# Sprite_CC1310_Development.net
KiCad netlist of a schematic drawn in EAGLE
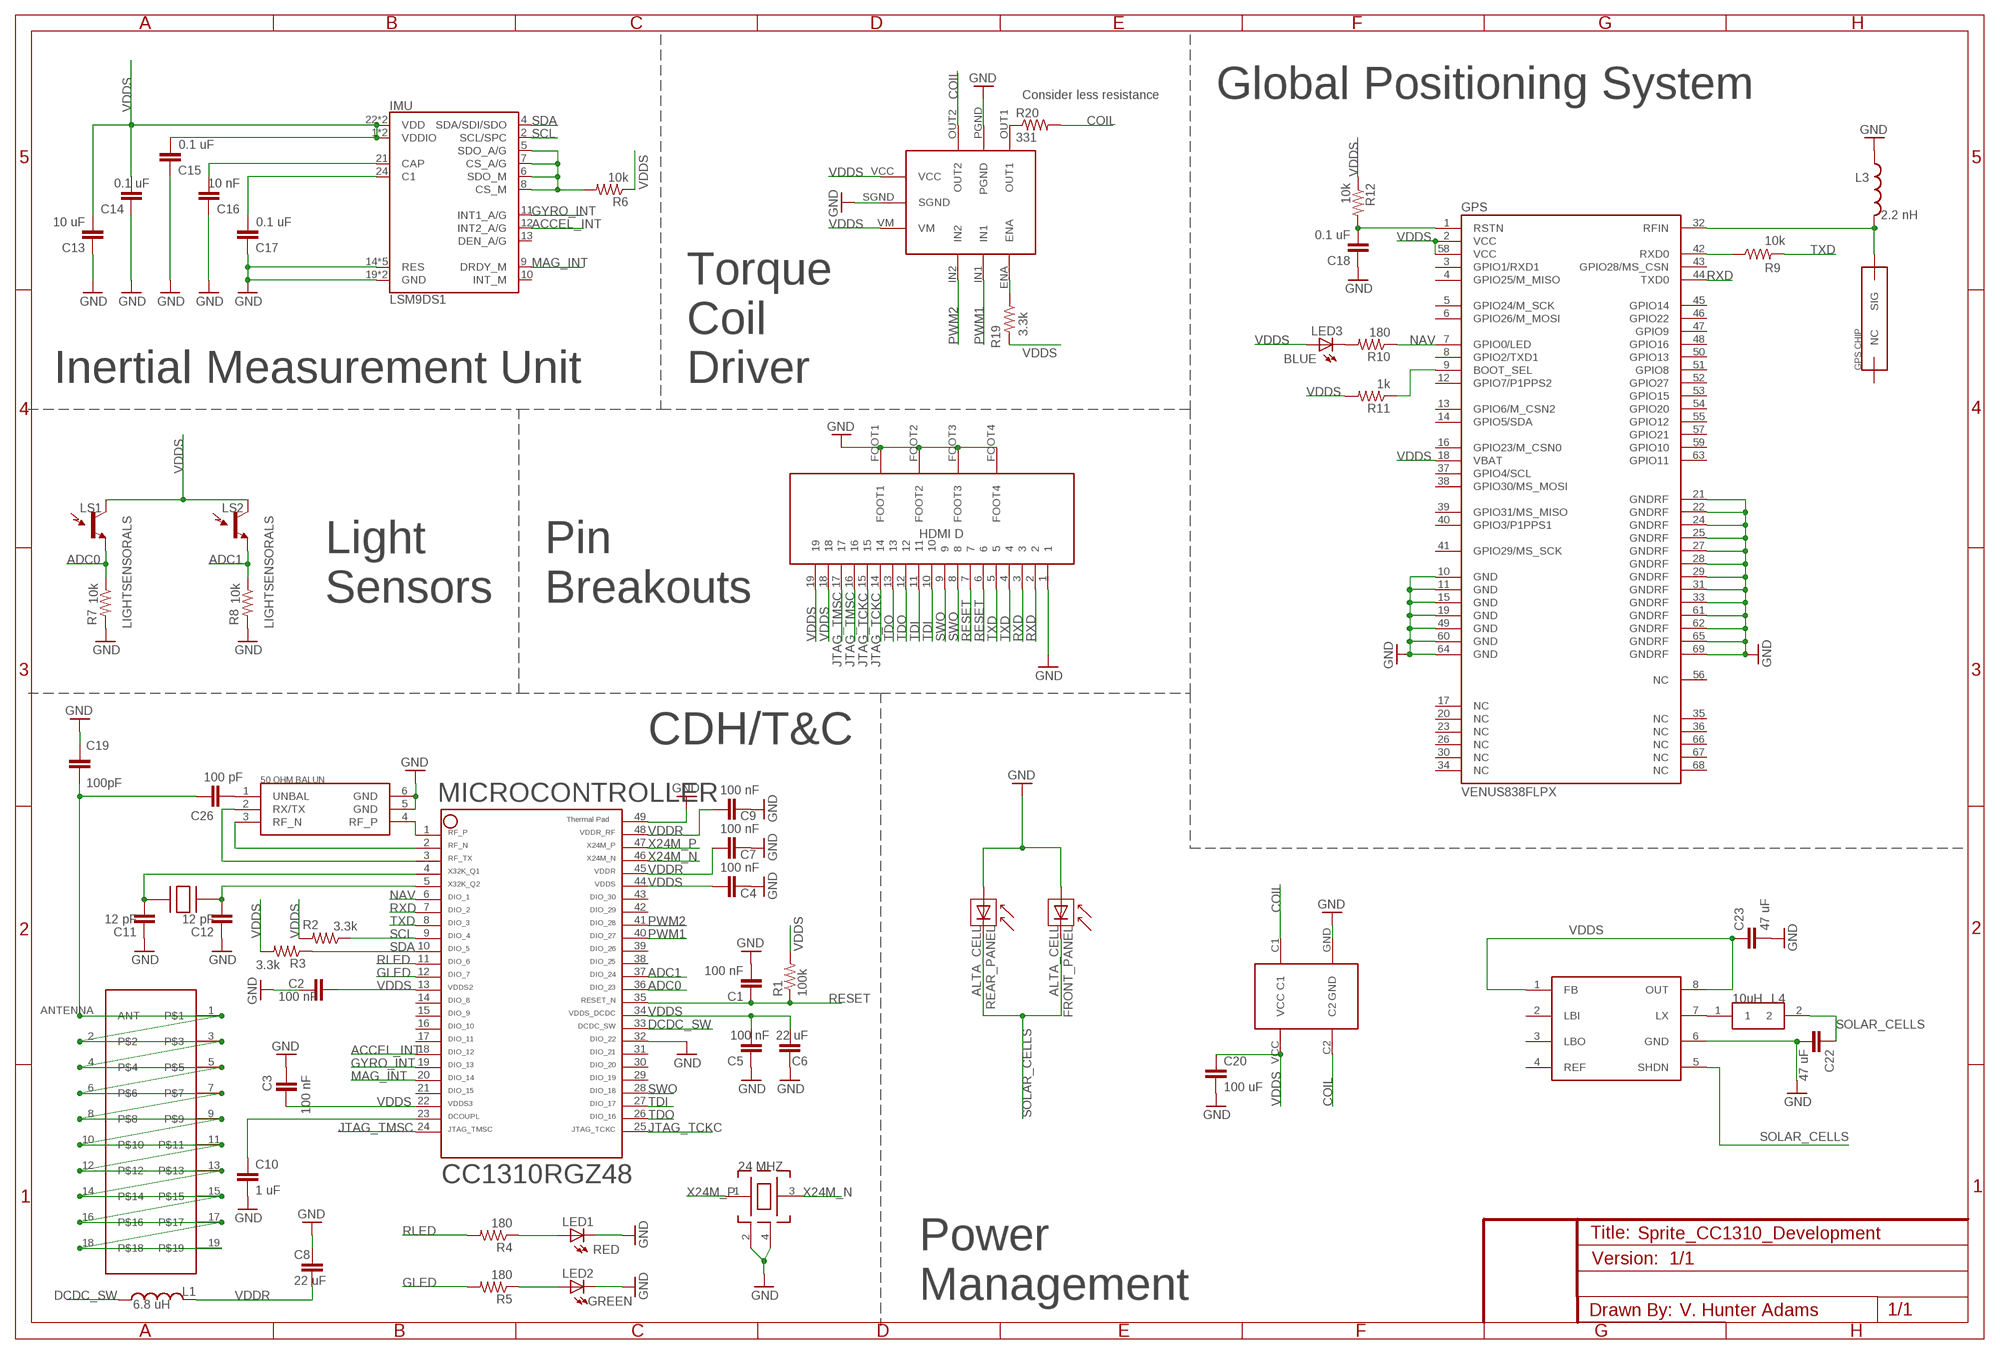
[diagram p0: schematic, sheet 1]

(export (version "E")
  (design (tool "Eeschema 10.0.6"))
  (components
    (comp (ref "32.768")
      (value "FC-135")
      (footprint "eagle-import:FC-135")
      (libsource (lib "eagle-import") (part "FC-135"))
    )
    (comp (ref "BALUN")
      (value "JOHANSON_BALUN")
      (footprint "eagle-import:JOHANSON_BALUN")
      (libsource (lib "eagle-import") (part "JOHANSON_BALUN"))
    )
    (comp (ref "C1")
      (value "100 nF")
      (footprint "eagle-import:0402-CAP")
      (libsource (lib "eagle-import") (part "CAP0402-CAP"))
    )
    (comp (ref "C2")
      (value "100 nF")
      (footprint "eagle-import:0402-CAP")
      (libsource (lib "eagle-import") (part "CAP0402-CAP"))
    )
    (comp (ref "C3")
      (value "100 nF")
      (footprint "eagle-import:0402-CAP")
      (libsource (lib "eagle-import") (part "CAP0402-CAP"))
    )
    (comp (ref "C4")
      (value "100 nF")
      (footprint "eagle-import:0402-CAP")
      (libsource (lib "eagle-import") (part "CAP0402-CAP"))
    )
    (comp (ref "C5")
      (value "100 nF")
      (footprint "eagle-import:0402-CAP")
      (libsource (lib "eagle-import") (part "CAP0402-CAP"))
    )
    (comp (ref "C6")
      (value "22 uF")
      (footprint "eagle-import:0402-CAP")
      (libsource (lib "eagle-import") (part "CAP0402-CAP"))
    )
    (comp (ref "C7")
      (value "100 nF")
      (footprint "eagle-import:0402-CAP")
      (libsource (lib "eagle-import") (part "CAP0402-CAP"))
    )
    (comp (ref "C8")
      (value "22 uF")
      (footprint "eagle-import:0402-CAP")
      (libsource (lib "eagle-import") (part "CAP0402-CAP"))
    )
    (comp (ref "C9")
      (value "100 nF")
      (footprint "eagle-import:0402-CAP")
      (libsource (lib "eagle-import") (part "CAP0402-CAP"))
    )
    (comp (ref "C10")
      (value "1 uF")
      (footprint "eagle-import:0402-CAP")
      (libsource (lib "eagle-import") (part "CAP0402-CAP"))
    )
    (comp (ref "C11")
      (value "12 pF")
      (footprint "eagle-import:0402-CAP")
      (libsource (lib "eagle-import") (part "CAP0402-CAP"))
    )
    (comp (ref "C12")
      (value "12 pF")
      (footprint "eagle-import:0402-CAP")
      (libsource (lib "eagle-import") (part "CAP0402-CAP"))
    )
    (comp (ref "C13")
      (value "10 uF")
      (footprint "eagle-import:0402-CAP")
      (libsource (lib "eagle-import") (part "CAP0402-CAP"))
    )
    (comp (ref "C14")
      (value "0.1 uF")
      (footprint "eagle-import:0402-CAP")
      (libsource (lib "eagle-import") (part "CAP0402-CAP"))
    )
    (comp (ref "C15")
      (value "0.1 uF")
      (footprint "eagle-import:0402-CAP")
      (libsource (lib "eagle-import") (part "CAP0402-CAP"))
    )
    (comp (ref "C16")
      (value "10 nF")
      (footprint "eagle-import:0402-CAP")
      (libsource (lib "eagle-import") (part "CAP0402-CAP"))
    )
    (comp (ref "C17")
      (value "0.1 uF")
      (footprint "eagle-import:0402-CAP")
      (libsource (lib "eagle-import") (part "CAP0402-CAP"))
    )
    (comp (ref "C18")
      (value "0.1 uF")
      (footprint "eagle-import:0402-CAP")
      (libsource (lib "eagle-import") (part "CAP0402-CAP"))
    )
    (comp (ref "C19")
      (value "100pF")
      (footprint "eagle-import:0603-CAP")
      (libsource (lib "eagle-import") (part "CAP0603-CAP"))
    )
    (comp (ref "C20")
      (value "100 uF")
      (footprint "eagle-import:0805")
      (libsource (lib "eagle-import") (part "CAP0805"))
    )
    (comp (ref "C22")
      (value "47 uF")
      (footprint "eagle-import:0805")
      (libsource (lib "eagle-import") (part "CAP0805"))
    )
    (comp (ref "C23")
      (value "47 uF")
      (footprint "eagle-import:0805")
      (libsource (lib "eagle-import") (part "CAP0805"))
    )
    (comp (ref "C26")
      (value "100 pF")
      (footprint "eagle-import:0402-CAP")
      (libsource (lib "eagle-import") (part "CAP0402-CAP"))
    )
    (comp (ref "FRONT_PANEL")
      (value "ALTA_CELL")
      (footprint "eagle-import:ALTA_CELL")
      (libsource (lib "eagle-import") (part "ALTA_CELL"))
    )
    (comp (ref "GPS")
      (value "VENUS838FLPX")
      (footprint "eagle-import:VENUS838FLPX")
      (libsource (lib "eagle-import") (part "VENUS838FLPX"))
    )
    (comp (ref "IMU")
      (value "LSM9DS1")
      (footprint "eagle-import:LGA24-8X4")
      (libsource (lib "eagle-import") (part "LSM9DS1"))
    )
    (comp (ref "L1")
      (value "6.8 uH")
      (footprint "eagle-import:0603")
      (libsource (lib "eagle-import") (part "INDUCTOR0603"))
    )
    (comp (ref "L3")
      (value "2.2 nH")
      (footprint "eagle-import:0603")
      (libsource (lib "eagle-import") (part "INDUCTOR0603"))
    )
    (comp (ref "L4")
      (value "10uH")
      (footprint "eagle-import:ASPI-0315FS")
      (libsource (lib "eagle-import") (part "ASPI-0315FS"))
    )
    (comp (ref "LED1")
      (value "RED")
      (footprint "eagle-import:LED-0603")
      (libsource (lib "eagle-import") (part "LED0603"))
    )
    (comp (ref "LED2")
      (value "GREEN")
      (footprint "eagle-import:LED-0603")
      (libsource (lib "eagle-import") (part "LED0603"))
    )
    (comp (ref "LED3")
      (value "BLUE")
      (footprint "eagle-import:LED-0603")
      (libsource (lib "eagle-import") (part "LED0603"))
    )
    (comp (ref "LS1")
      (value "LIGHTSENSORALS")
      (footprint "eagle-import:ALS-PT19")
      (libsource (lib "eagle-import") (part "LIGHTSENSORALS"))
    )
    (comp (ref "LS2")
      (value "LIGHTSENSORALS")
      (footprint "eagle-import:ALS-PT19")
      (libsource (lib "eagle-import") (part "LIGHTSENSORALS"))
    )
    (comp (ref "MICROCONTROLLER")
      (value "CC1310")
      (footprint "eagle-import:CC1310")
      (libsource (lib "eagle-import") (part "CC1310"))
    )
    (comp (ref "R1")
      (value "100k")
      (footprint "eagle-import:0402-RES")
      (libsource (lib "eagle-import") (part "RESISTOR0402-RES"))
    )
    (comp (ref "R2")
      (value "3.3k")
      (footprint "eagle-import:0402-RES")
      (libsource (lib "eagle-import") (part "RESISTOR0402-RES"))
    )
    (comp (ref "R3")
      (value "3.3k")
      (footprint "eagle-import:0402-RES")
      (libsource (lib "eagle-import") (part "RESISTOR0402-RES"))
    )
    (comp (ref "R4")
      (value "180")
      (footprint "eagle-import:0402-RES")
      (libsource (lib "eagle-import") (part "RESISTOR0402-RES"))
    )
    (comp (ref "R5")
      (value "180")
      (footprint "eagle-import:0402-RES")
      (libsource (lib "eagle-import") (part "RESISTOR0402-RES"))
    )
    (comp (ref "R6")
      (value "10k")
      (footprint "eagle-import:0402-RES")
      (libsource (lib "eagle-import") (part "RESISTOR0402-RES"))
    )
    (comp (ref "R7")
      (value "10k")
      (footprint "eagle-import:0402-RES")
      (libsource (lib "eagle-import") (part "RESISTOR0402-RES"))
    )
    (comp (ref "R8")
      (value "10k")
      (footprint "eagle-import:0402-RES")
      (libsource (lib "eagle-import") (part "RESISTOR0402-RES"))
    )
    (comp (ref "R9")
      (value "10k")
      (footprint "eagle-import:0402-RES")
      (libsource (lib "eagle-import") (part "RESISTOR0402-RES"))
    )
    (comp (ref "R10")
      (value "180")
      (footprint "eagle-import:0402-RES")
      (libsource (lib "eagle-import") (part "RESISTOR0402-RES"))
    )
    (comp (ref "R11")
      (value "1k")
      (footprint "eagle-import:0402-RES")
      (libsource (lib "eagle-import") (part "RESISTOR0402-RES"))
    )
    (comp (ref "R12")
      (value "10k")
      (footprint "eagle-import:0402-RES")
      (libsource (lib "eagle-import") (part "RESISTOR0402-RES"))
    )
    (comp (ref "R19")
      (value "3.3k")
      (footprint "eagle-import:0402-RES")
      (libsource (lib "eagle-import") (part "RESISTOR0402-RES"))
    )
    (comp (ref "R20")
      (value "331")
      (footprint "eagle-import:0402-RES")
      (libsource (lib "eagle-import") (part "RESISTOR0402-RES"))
    )
    (comp (ref "REAR_PANEL")
      (value "ALTA_CELL")
      (footprint "eagle-import:ALTA_CELL")
      (libsource (lib "eagle-import") (part "ALTA_CELL"))
    )
    (comp (ref "TSX3225")
      (value "TSX-3225")
      (footprint "eagle-import:TSX-3225")
      (libsource (lib "eagle-import") (part "TSX-3225"))
    )
    (comp (ref "U$2")
      (value "LV8417CS")
      (footprint "eagle-import:LV8417CS")
      (libsource (lib "eagle-import") (part "LV8417CS"))
    )
    (comp (ref "U$4")
      (value "PANASONIC_RECTIFIER")
      (footprint "eagle-import:PANASONIC_RECTIFIER")
      (libsource (lib "eagle-import") (part "PANASONIC_RECTIFIER"))
    )
    (comp (ref "U$5")
      (value "JOHANSON_GPS_CHIP")
      (footprint "eagle-import:JOHANSON_GPS_CHIP")
      (libsource (lib "eagle-import") (part "JOHANSON_GPS_CHIP"))
    )
    (comp (ref "U$6")
      (value "PCB_ANTENNA")
      (footprint "eagle-import:PCB_ANTENNA")
      (libsource (lib "eagle-import") (part "PCB_ANTENNA"))
    )
    (comp (ref "U$8")
      (value "L6920")
      (footprint "eagle-import:L6920")
      (libsource (lib "eagle-import") (part "L6920"))
    )
    (comp (ref "U$9")
      (value "HDMID")
      (footprint "eagle-import:HDMID")
      (libsource (lib "eagle-import") (part "HDMID"))
    )
  )
  (nets
    (net (code "1") (name "/ACCEL_INT") (class "Default")
      (node (ref "IMU") (pin "12") (pinfunction "INT2_A/G_12") (pintype "bidirectional"))
      (node (ref "MICROCONTROLLER") (pin "18") (pinfunction "18_18") (pintype "bidirectional"))
    )
    (net (code "2") (name "/ADC0") (class "Default")
      (node (ref "LS1") (pin "E") (pinfunction "E1_E") (pintype "passive"))
      (node (ref "MICROCONTROLLER") (pin "36") (pinfunction "36_36") (pintype "bidirectional"))
      (node (ref "R7") (pin "1") (pinfunction "1_1") (pintype "passive"))
    )
    (net (code "3") (name "/ADC1") (class "Default")
      (node (ref "LS2") (pin "E") (pinfunction "E1_E") (pintype "passive"))
      (node (ref "MICROCONTROLLER") (pin "37") (pinfunction "37_37") (pintype "bidirectional"))
      (node (ref "R8") (pin "1") (pinfunction "1_1") (pintype "passive"))
    )
    (net (code "4") (name "/COIL") (class "Default")
      (node (ref "R20") (pin "2") (pinfunction "2_2") (pintype "passive"))
      (node (ref "U$2") (pin "OUT2") (pinfunction "OUT2_OUT2") (pintype "bidirectional"))
      (node (ref "U$4") (pin "C1") (pinfunction "C1_C1") (pintype "bidirectional"))
      (node (ref "U$4") (pin "C2") (pinfunction "C2_C2") (pintype "bidirectional"))
    )
    (net (code "5") (name "/DCDC_SW") (class "Default")
      (node (ref "L1") (pin "1") (pinfunction "1_1") (pintype "passive"))
      (node (ref "MICROCONTROLLER") (pin "33") (pinfunction "33_33") (pintype "power_in"))
    )
    (net (code "6") (name "/GLED") (class "Default")
      (node (ref "MICROCONTROLLER") (pin "12") (pinfunction "12_12") (pintype "bidirectional"))
      (node (ref "R5") (pin "2") (pinfunction "2_2") (pintype "passive"))
    )
    (net (code "7") (name "/GYRO_INT") (class "Default")
      (node (ref "IMU") (pin "11") (pinfunction "INT1_A/G_11") (pintype "bidirectional"))
      (node (ref "MICROCONTROLLER") (pin "19") (pinfunction "19_19") (pintype "bidirectional"))
    )
    (net (code "8") (name "/JTAG_TCKC") (class "Default")
      (node (ref "MICROCONTROLLER") (pin "25") (pinfunction "25_25") (pintype "input"))
      (node (ref "U$9") (pin "14") (pinfunction "14_14") (pintype "bidirectional"))
      (node (ref "U$9") (pin "15") (pinfunction "15_15") (pintype "bidirectional"))
    )
    (net (code "9") (name "/JTAG_TMSC") (class "Default")
      (node (ref "MICROCONTROLLER") (pin "24") (pinfunction "24_24") (pintype "bidirectional"))
      (node (ref "U$9") (pin "16") (pinfunction "16_16") (pintype "bidirectional"))
      (node (ref "U$9") (pin "17") (pinfunction "17_17") (pintype "bidirectional"))
    )
    (net (code "10") (name "/MAG_INT") (class "Default")
      (node (ref "IMU") (pin "9") (pinfunction "DRDY_M_9") (pintype "bidirectional"))
      (node (ref "MICROCONTROLLER") (pin "20") (pinfunction "20_20") (pintype "bidirectional"))
    )
    (net (code "11") (name "/NAV") (class "Default")
      (node (ref "GPS") (pin "7") (pinfunction "GPIO0/LED_7") (pintype "bidirectional"))
      (node (ref "MICROCONTROLLER") (pin "6") (pinfunction "6_6") (pintype "bidirectional"))
      (node (ref "R10") (pin "1") (pinfunction "1_1") (pintype "passive"))
    )
    (net (code "12") (name "/PWM1") (class "Default")
      (node (ref "MICROCONTROLLER") (pin "40") (pinfunction "40_40") (pintype "bidirectional"))
      (node (ref "U$2") (pin "IN1") (pinfunction "IN1_IN1") (pintype "bidirectional"))
    )
    (net (code "13") (name "/PWM2") (class "Default")
      (node (ref "MICROCONTROLLER") (pin "41") (pinfunction "41_41") (pintype "bidirectional"))
      (node (ref "U$2") (pin "IN2") (pinfunction "IN2_IN2") (pintype "bidirectional"))
    )
    (net (code "14") (name "/RESET") (class "Default")
      (node (ref "C1") (pin "1") (pinfunction "1_1") (pintype "passive"))
      (node (ref "MICROCONTROLLER") (pin "35") (pinfunction "35_35") (pintype "input"))
      (node (ref "R1") (pin "1") (pinfunction "1_1") (pintype "passive"))
      (node (ref "U$9") (pin "6") (pinfunction "6_6") (pintype "bidirectional"))
      (node (ref "U$9") (pin "7") (pinfunction "7_7") (pintype "bidirectional"))
    )
    (net (code "15") (name "/RLED") (class "Default")
      (node (ref "MICROCONTROLLER") (pin "11") (pinfunction "11_11") (pintype "bidirectional"))
      (node (ref "R4") (pin "2") (pinfunction "2_2") (pintype "passive"))
    )
    (net (code "16") (name "/RXD") (class "Default")
      (node (ref "GPS") (pin "44") (pinfunction "TXD0_44") (pintype "bidirectional"))
      (node (ref "MICROCONTROLLER") (pin "7") (pinfunction "7_7") (pintype "bidirectional"))
      (node (ref "U$9") (pin "2") (pinfunction "2_2") (pintype "bidirectional"))
      (node (ref "U$9") (pin "3") (pinfunction "3_3") (pintype "bidirectional"))
    )
    (net (code "17") (name "/SCL") (class "Default")
      (node (ref "IMU") (pin "2") (pinfunction "SCL/SPC_2") (pintype "bidirectional"))
      (node (ref "MICROCONTROLLER") (pin "9") (pinfunction "9_9") (pintype "bidirectional"))
      (node (ref "R2") (pin "1") (pinfunction "1_1") (pintype "passive"))
    )
    (net (code "18") (name "/SDA") (class "Default")
      (node (ref "IMU") (pin "4") (pinfunction "SDA/SDI/SDO_4") (pintype "bidirectional"))
      (node (ref "MICROCONTROLLER") (pin "10") (pinfunction "10_10") (pintype "bidirectional"))
      (node (ref "R3") (pin "1") (pinfunction "1_1") (pintype "passive"))
    )
    (net (code "19") (name "/SOLAR_CELLS") (class "Default")
      (node (ref "C22") (pin "1") (pinfunction "1_1") (pintype "passive"))
      (node (ref "FRONT_PANEL") (pin "+") (pinfunction "+_+") (pintype "passive"))
      (node (ref "L4") (pin "2") (pinfunction "2_2") (pintype "bidirectional"))
      (node (ref "REAR_PANEL") (pin "+") (pinfunction "+_+") (pintype "passive"))
      (node (ref "U$8") (pin "5") (pinfunction "SHDN_5") (pintype "bidirectional"))
    )
    (net (code "20") (name "/SWO") (class "Default")
      (node (ref "MICROCONTROLLER") (pin "28") (pinfunction "28_28") (pintype "bidirectional"))
      (node (ref "U$9") (pin "8") (pinfunction "8_8") (pintype "bidirectional"))
      (node (ref "U$9") (pin "9") (pinfunction "9_9") (pintype "bidirectional"))
    )
    (net (code "21") (name "/TDI") (class "Default")
      (node (ref "MICROCONTROLLER") (pin "27") (pinfunction "27_27") (pintype "bidirectional"))
      (node (ref "U$9") (pin "10") (pinfunction "10_10") (pintype "bidirectional"))
      (node (ref "U$9") (pin "11") (pinfunction "11_11") (pintype "bidirectional"))
    )
    (net (code "22") (name "/TDO") (class "Default")
      (node (ref "MICROCONTROLLER") (pin "26") (pinfunction "26_26") (pintype "bidirectional"))
      (node (ref "U$9") (pin "12") (pinfunction "12_12") (pintype "bidirectional"))
      (node (ref "U$9") (pin "13") (pinfunction "13_13") (pintype "bidirectional"))
    )
    (net (code "23") (name "/TXD") (class "Default")
      (node (ref "MICROCONTROLLER") (pin "8") (pinfunction "8_8") (pintype "bidirectional"))
      (node (ref "R9") (pin "2") (pinfunction "2_2") (pintype "passive"))
      (node (ref "U$9") (pin "4") (pinfunction "4_4") (pintype "bidirectional"))
      (node (ref "U$9") (pin "5") (pinfunction "5_5") (pintype "bidirectional"))
    )
    (net (code "24") (name "/VDDR") (class "Default")
      (node (ref "C7") (pin "1") (pinfunction "1_1") (pintype "passive"))
      (node (ref "C8") (pin "1") (pinfunction "1_1") (pintype "passive"))
      (node (ref "C9") (pin "1") (pinfunction "1_1") (pintype "passive"))
      (node (ref "L1") (pin "2") (pinfunction "2_2") (pintype "passive"))
      (node (ref "MICROCONTROLLER") (pin "45") (pinfunction "45_45") (pintype "power_in"))
      (node (ref "MICROCONTROLLER") (pin "48") (pinfunction "48_48") (pintype "power_in"))
    )
    (net (code "25") (name "/VDDS") (class "Default")
      (node (ref "C13") (pin "1") (pinfunction "1_1") (pintype "passive"))
      (node (ref "C14") (pin "1") (pinfunction "1_1") (pintype "passive"))
      (node (ref "C15") (pin "1") (pinfunction "1_1") (pintype "passive"))
      (node (ref "C2") (pin "1") (pinfunction "1_1") (pintype "passive"))
      (node (ref "C20") (pin "1") (pinfunction "1_1") (pintype "passive"))
      (node (ref "C23") (pin "1") (pinfunction "1_1") (pintype "passive"))
      (node (ref "C3") (pin "1") (pinfunction "1_1") (pintype "passive"))
      (node (ref "C4") (pin "1") (pinfunction "1_1") (pintype "passive"))
      (node (ref "C5") (pin "1") (pinfunction "1_1") (pintype "passive"))
      (node (ref "C6") (pin "1") (pinfunction "1_1") (pintype "passive"))
      (node (ref "GPS") (pin "18") (pinfunction "VBAT_18") (pintype "bidirectional"))
      (node (ref "GPS") (pin "2") (pinfunction "VCC_2") (pintype "bidirectional"))
      (node (ref "GPS") (pin "58") (pinfunction "VCC_58") (pintype "bidirectional"))
      (node (ref "IMU") (pin "1") (pinfunction "VDDIO_1") (pintype "bidirectional"))
      (node (ref "IMU") (pin "22") (pinfunction "VDD_22") (pintype "bidirectional"))
      (node (ref "IMU") (pin "23") (pinfunction "VDD_23") (pintype "bidirectional"))
      (node (ref "IMU") (pin "3") (pinfunction "VDDIO_3") (pintype "bidirectional"))
      (node (ref "LED3") (pin "A") (pinfunction "A_A") (pintype "passive"))
      (node (ref "LS1") (pin "C") (pinfunction "C1_C") (pintype "passive"))
      (node (ref "LS2") (pin "C") (pinfunction "C1_C") (pintype "passive"))
      (node (ref "MICROCONTROLLER") (pin "13") (pinfunction "13_13") (pintype "bidirectional"))
      (node (ref "MICROCONTROLLER") (pin "22") (pinfunction "22_22") (pintype "power_in"))
      (node (ref "MICROCONTROLLER") (pin "34") (pinfunction "34_34") (pintype "power_in"))
      (node (ref "MICROCONTROLLER") (pin "44") (pinfunction "44_44") (pintype "power_in"))
      (node (ref "R1") (pin "2") (pinfunction "2_2") (pintype "passive"))
      (node (ref "R11") (pin "2") (pinfunction "2_2") (pintype "passive"))
      (node (ref "R12") (pin "1") (pinfunction "1_1") (pintype "passive"))
      (node (ref "R19") (pin "2") (pinfunction "2_2") (pintype "passive"))
      (node (ref "R2") (pin "2") (pinfunction "2_2") (pintype "passive"))
      (node (ref "R3") (pin "2") (pinfunction "2_2") (pintype "passive"))
      (node (ref "R6") (pin "1") (pinfunction "1_1") (pintype "passive"))
      (node (ref "U$2") (pin "VCC") (pinfunction "VCC_VCC") (pintype "bidirectional"))
      (node (ref "U$2") (pin "VM") (pinfunction "VM_VM") (pintype "bidirectional"))
      (node (ref "U$4") (pin "VCC") (pinfunction "VCC_VCC") (pintype "bidirectional"))
      (node (ref "U$8") (pin "1") (pinfunction "FB_1") (pintype "bidirectional"))
      (node (ref "U$8") (pin "8") (pinfunction "OUT_8") (pintype "bidirectional"))
      (node (ref "U$9") (pin "18") (pinfunction "18_18") (pintype "bidirectional"))
      (node (ref "U$9") (pin "19") (pinfunction "19_19") (pintype "bidirectional"))
    )
    (net (code "26") (name "/X24M_N") (class "Default")
      (node (ref "MICROCONTROLLER") (pin "46") (pinfunction "46_46") (pintype "bidirectional"))
      (node (ref "TSX3225") (pin "3") (pinfunction "3_3") (pintype "bidirectional"))
    )
    (net (code "27") (name "/X24M_P") (class "Default")
      (node (ref "MICROCONTROLLER") (pin "47") (pinfunction "47_47") (pintype "input"))
      (node (ref "TSX3225") (pin "1") (pinfunction "1_1") (pintype "bidirectional"))
    )
    (net (code "28") (name "GND") (class "Default")
      (node (ref "BALUN") (pin "5") (pinfunction "GND_5") (pintype "bidirectional"))
      (node (ref "BALUN") (pin "6") (pinfunction "GND_6") (pintype "bidirectional"))
      (node (ref "C1") (pin "2") (pinfunction "2_2") (pintype "passive"))
      (node (ref "C10") (pin "2") (pinfunction "2_2") (pintype "passive"))
      (node (ref "C11") (pin "2") (pinfunction "2_2") (pintype "passive"))
      (node (ref "C12") (pin "2") (pinfunction "2_2") (pintype "passive"))
      (node (ref "C13") (pin "2") (pinfunction "2_2") (pintype "passive"))
      (node (ref "C14") (pin "2") (pinfunction "2_2") (pintype "passive"))
      (node (ref "C15") (pin "2") (pinfunction "2_2") (pintype "passive"))
      (node (ref "C16") (pin "2") (pinfunction "2_2") (pintype "passive"))
      (node (ref "C17") (pin "2") (pinfunction "2_2") (pintype "passive"))
      (node (ref "C18") (pin "2") (pinfunction "2_2") (pintype "passive"))
      (node (ref "C19") (pin "1") (pinfunction "1_1") (pintype "passive"))
      (node (ref "C2") (pin "2") (pinfunction "2_2") (pintype "passive"))
      (node (ref "C20") (pin "2") (pinfunction "2_2") (pintype "passive"))
      (node (ref "C22") (pin "2") (pinfunction "2_2") (pintype "passive"))
      (node (ref "C23") (pin "2") (pinfunction "2_2") (pintype "passive"))
      (node (ref "C3") (pin "2") (pinfunction "2_2") (pintype "passive"))
      (node (ref "C4") (pin "2") (pinfunction "2_2") (pintype "passive"))
      (node (ref "C5") (pin "2") (pinfunction "2_2") (pintype "passive"))
      (node (ref "C6") (pin "2") (pinfunction "2_2") (pintype "passive"))
      (node (ref "C7") (pin "2") (pinfunction "2_2") (pintype "passive"))
      (node (ref "C8") (pin "2") (pinfunction "2_2") (pintype "passive"))
      (node (ref "C9") (pin "2") (pinfunction "2_2") (pintype "passive"))
      (node (ref "FRONT_PANEL") (pin "-") (pinfunction "-_-") (pintype "passive"))
      (node (ref "GPS") (pin "10") (pinfunction "GND_10") (pintype "bidirectional"))
      (node (ref "GPS") (pin "11") (pinfunction "GND_11") (pintype "bidirectional"))
      (node (ref "GPS") (pin "15") (pinfunction "GND_15") (pintype "bidirectional"))
      (node (ref "GPS") (pin "19") (pinfunction "GND_19") (pintype "bidirectional"))
      (node (ref "GPS") (pin "21") (pinfunction "GNDRF_21") (pintype "bidirectional"))
      (node (ref "GPS") (pin "22") (pinfunction "GNDRF_22") (pintype "bidirectional"))
      (node (ref "GPS") (pin "24") (pinfunction "GNDRF_24") (pintype "bidirectional"))
      (node (ref "GPS") (pin "25") (pinfunction "GNDRF_25") (pintype "bidirectional"))
      (node (ref "GPS") (pin "27") (pinfunction "GNDRF_27") (pintype "bidirectional"))
      (node (ref "GPS") (pin "28") (pinfunction "GNDRF_28") (pintype "bidirectional"))
      (node (ref "GPS") (pin "29") (pinfunction "GNDRF_29") (pintype "bidirectional"))
      (node (ref "GPS") (pin "31") (pinfunction "GNDRF_31") (pintype "bidirectional"))
      (node (ref "GPS") (pin "33") (pinfunction "GNDRF_33") (pintype "bidirectional"))
      (node (ref "GPS") (pin "49") (pinfunction "GND_49") (pintype "bidirectional"))
      (node (ref "GPS") (pin "60") (pinfunction "GND_60") (pintype "bidirectional"))
      (node (ref "GPS") (pin "61") (pinfunction "GNDRF_61") (pintype "bidirectional"))
      (node (ref "GPS") (pin "62") (pinfunction "GNDRF_62") (pintype "bidirectional"))
      (node (ref "GPS") (pin "64") (pinfunction "GND_64") (pintype "bidirectional"))
      (node (ref "GPS") (pin "65") (pinfunction "GNDRF_65") (pintype "bidirectional"))
      (node (ref "GPS") (pin "69") (pinfunction "GNDRF_69") (pintype "bidirectional"))
      (node (ref "IMU") (pin "14") (pinfunction "RES_14") (pintype "bidirectional"))
      (node (ref "IMU") (pin "15") (pinfunction "RES_15") (pintype "bidirectional"))
      (node (ref "IMU") (pin "16") (pinfunction "RES_16") (pintype "bidirectional"))
      (node (ref "IMU") (pin "17") (pinfunction "RES_17") (pintype "bidirectional"))
      (node (ref "IMU") (pin "18") (pinfunction "RES_18") (pintype "bidirectional"))
      (node (ref "IMU") (pin "19") (pinfunction "GND_19") (pintype "bidirectional"))
      (node (ref "IMU") (pin "20") (pinfunction "GND_20") (pintype "bidirectional"))
      (node (ref "L3") (pin "1") (pinfunction "1_1") (pintype "passive"))
      (node (ref "LED1") (pin "C") (pinfunction "C_C") (pintype "passive"))
      (node (ref "LED2") (pin "C") (pinfunction "C_C") (pintype "passive"))
      (node (ref "MICROCONTROLLER") (pin "32") (pinfunction "32_32") (pintype "bidirectional"))
      (node (ref "MICROCONTROLLER") (pin "49") (pinfunction "49_49") (pintype "input"))
      (node (ref "R7") (pin "2") (pinfunction "2_2") (pintype "passive"))
      (node (ref "R8") (pin "2") (pinfunction "2_2") (pintype "passive"))
      (node (ref "REAR_PANEL") (pin "-") (pinfunction "-_-") (pintype "passive"))
      (node (ref "TSX3225") (pin "2") (pinfunction "2_2") (pintype "bidirectional"))
      (node (ref "TSX3225") (pin "4") (pinfunction "4_4") (pintype "bidirectional"))
      (node (ref "U$2") (pin "PGND") (pinfunction "PGND_PGND") (pintype "bidirectional"))
      (node (ref "U$2") (pin "SGND") (pinfunction "SGND_SGND") (pintype "bidirectional"))
      (node (ref "U$4") (pin "GND") (pinfunction "GND_GND") (pintype "bidirectional"))
      (node (ref "U$8") (pin "6") (pinfunction "GND_6") (pintype "bidirectional"))
      (node (ref "U$9") (pin "1") (pinfunction "1_1") (pintype "bidirectional"))
      (node (ref "U$9") (pin "FOOT1") (pinfunction "FOOT1_FOOT1") (pintype "bidirectional"))
      (node (ref "U$9") (pin "FOOT2") (pinfunction "FOOT2_FOOT2") (pintype "bidirectional"))
      (node (ref "U$9") (pin "FOOT3") (pinfunction "FOOT3_FOOT3") (pintype "bidirectional"))
      (node (ref "U$9") (pin "FOOT4") (pinfunction "FOOT4_FOOT4") (pintype "bidirectional"))
    )
    (net (code "29") (name "Net-(32.768-PadP1)") (class "Default")
      (node (ref "32.768") (pin "P1") (pinfunction "P1_P1") (pintype "bidirectional"))
      (node (ref "C12") (pin "1") (pinfunction "1_1") (pintype "passive"))
      (node (ref "MICROCONTROLLER") (pin "5") (pinfunction "5_5") (pintype "bidirectional"))
    )
    (net (code "30") (name "Net-(32.768-PadP2)") (class "Default")
      (node (ref "32.768") (pin "P2") (pinfunction "P2_P2") (pintype "bidirectional"))
      (node (ref "C11") (pin "1") (pinfunction "1_1") (pintype "passive"))
      (node (ref "MICROCONTROLLER") (pin "4") (pinfunction "4_4") (pintype "bidirectional"))
    )
    (net (code "31") (name "Net-(BALUN-RF_N)") (class "Default")
      (node (ref "BALUN") (pin "3") (pinfunction "RF_N_3") (pintype "bidirectional"))
      (node (ref "MICROCONTROLLER") (pin "2") (pinfunction "2_2") (pintype "bidirectional"))
    )
    (net (code "32") (name "Net-(BALUN-RF_P)") (class "Default")
      (node (ref "BALUN") (pin "4") (pinfunction "RF_P_4") (pintype "bidirectional"))
      (node (ref "MICROCONTROLLER") (pin "1") (pinfunction "1_1") (pintype "bidirectional"))
    )
    (net (code "33") (name "Net-(BALUN-RX{slash}TX)") (class "Default")
      (node (ref "BALUN") (pin "2") (pinfunction "RX/TX_2") (pintype "bidirectional"))
      (node (ref "MICROCONTROLLER") (pin "3") (pinfunction "3_3") (pintype "bidirectional"))
    )
    (net (code "34") (name "Net-(BALUN-UNBAL)") (class "Default")
      (node (ref "BALUN") (pin "1") (pinfunction "UNBAL_1") (pintype "bidirectional"))
      (node (ref "C26") (pin "2") (pinfunction "2_2") (pintype "passive"))
    )
    (net (code "35") (name "Net-(C10-Pad1)") (class "Default")
      (node (ref "C10") (pin "1") (pinfunction "1_1") (pintype "passive"))
      (node (ref "MICROCONTROLLER") (pin "23") (pinfunction "23_23") (pintype "bidirectional"))
    )
    (net (code "36") (name "Net-(GPS-BOOT_SEL)") (class "Default")
      (node (ref "GPS") (pin "9") (pinfunction "BOOT_SEL_9") (pintype "bidirectional"))
      (node (ref "R11") (pin "1") (pinfunction "1_1") (pintype "passive"))
    )
    (net (code "37") (name "Net-(GPS-RFIN)") (class "Default")
      (node (ref "GPS") (pin "32") (pinfunction "RFIN_32") (pintype "bidirectional"))
      (node (ref "L3") (pin "2") (pinfunction "2_2") (pintype "passive"))
      (node (ref "U$5") (pin "SIG") (pinfunction "SIG_SIG") (pintype "bidirectional"))
    )
    (net (code "38") (name "Net-(GPS-RSTN)") (class "Default")
      (node (ref "C18") (pin "1") (pinfunction "1_1") (pintype "passive"))
      (node (ref "GPS") (pin "1") (pinfunction "RSTN_1") (pintype "bidirectional"))
      (node (ref "R12") (pin "2") (pinfunction "2_2") (pintype "passive"))
    )
    (net (code "39") (name "Net-(GPS-RXD0)") (class "Default")
      (node (ref "GPS") (pin "42") (pinfunction "RXD0_42") (pintype "bidirectional"))
      (node (ref "R9") (pin "1") (pinfunction "1_1") (pintype "passive"))
    )
    (net (code "40") (name "Net-(IMU-C1)") (class "Default")
      (node (ref "C17") (pin "1") (pinfunction "1_1") (pintype "passive"))
      (node (ref "IMU") (pin "24") (pinfunction "C1_24") (pintype "bidirectional"))
    )
    (net (code "41") (name "Net-(IMU-CAP)") (class "Default")
      (node (ref "C16") (pin "1") (pinfunction "1_1") (pintype "passive"))
      (node (ref "IMU") (pin "21") (pinfunction "CAP_21") (pintype "bidirectional"))
    )
    (net (code "42") (name "Net-(IMU-CS_A{slash}G)") (class "Default")
      (node (ref "IMU") (pin "5") (pinfunction "SDO_A/G_5") (pintype "bidirectional"))
      (node (ref "IMU") (pin "6") (pinfunction "SDO_M_6") (pintype "bidirectional"))
      (node (ref "IMU") (pin "7") (pinfunction "CS_A/G_7") (pintype "bidirectional"))
      (node (ref "IMU") (pin "8") (pinfunction "CS_M_8") (pintype "bidirectional"))
      (node (ref "R6") (pin "2") (pinfunction "2_2") (pintype "passive"))
    )
    (net (code "43") (name "Net-(LED1-PadA)") (class "Default")
      (node (ref "LED1") (pin "A") (pinfunction "A_A") (pintype "passive"))
      (node (ref "R4") (pin "1") (pinfunction "1_1") (pintype "passive"))
    )
    (net (code "44") (name "Net-(LED2-PadA)") (class "Default")
      (node (ref "LED2") (pin "A") (pinfunction "A_A") (pintype "passive"))
      (node (ref "R5") (pin "1") (pinfunction "1_1") (pintype "passive"))
    )
    (net (code "45") (name "Net-(LED3-PadC)") (class "Default")
      (node (ref "LED3") (pin "C") (pinfunction "C_C") (pintype "passive"))
      (node (ref "R10") (pin "2") (pinfunction "2_2") (pintype "passive"))
    )
    (net (code "46") (name "Net-(R19-Pad1)") (class "Default")
      (node (ref "R19") (pin "1") (pinfunction "1_1") (pintype "passive"))
      (node (ref "U$2") (pin "ENA") (pinfunction "ENA_ENA") (pintype "bidirectional"))
    )
    (net (code "47") (name "Net-(R20-Pad1)") (class "Default")
      (node (ref "R20") (pin "1") (pinfunction "1_1") (pintype "passive"))
      (node (ref "U$2") (pin "OUT1") (pinfunction "OUT1_OUT1") (pintype "bidirectional"))
    )
    (net (code "48") (name "Net-(U$6-ANT)") (class "Default")
      (node (ref "C19") (pin "2") (pinfunction "2_2") (pintype "passive"))
      (node (ref "C26") (pin "1") (pinfunction "1_1") (pintype "passive"))
      (node (ref "U$6") (pin "1") (pinfunction "P$1_1") (pintype "bidirectional"))
      (node (ref "U$6") (pin "10") (pinfunction "P$10_10") (pintype "bidirectional"))
      (node (ref "U$6") (pin "11") (pinfunction "P$11_11") (pintype "bidirectional"))
      (node (ref "U$6") (pin "12") (pinfunction "P$12_12") (pintype "bidirectional"))
      (node (ref "U$6") (pin "13") (pinfunction "P$13_13") (pintype "bidirectional"))
      (node (ref "U$6") (pin "14") (pinfunction "P$14_14") (pintype "bidirectional"))
      (node (ref "U$6") (pin "15") (pinfunction "P$15_15") (pintype "bidirectional"))
      (node (ref "U$6") (pin "16") (pinfunction "P$16_16") (pintype "bidirectional"))
      (node (ref "U$6") (pin "17") (pinfunction "P$17_17") (pintype "bidirectional"))
      (node (ref "U$6") (pin "18") (pinfunction "P$18_18") (pintype "bidirectional"))
      (node (ref "U$6") (pin "19") (pinfunction "P$19_19") (pintype "bidirectional"))
      (node (ref "U$6") (pin "2") (pinfunction "P$2_2") (pintype "bidirectional"))
      (node (ref "U$6") (pin "3") (pinfunction "P$3_3") (pintype "bidirectional"))
      (node (ref "U$6") (pin "4") (pinfunction "P$4_4") (pintype "bidirectional"))
      (node (ref "U$6") (pin "5") (pinfunction "P$5_5") (pintype "bidirectional"))
      (node (ref "U$6") (pin "6") (pinfunction "P$6_6") (pintype "bidirectional"))
      (node (ref "U$6") (pin "7") (pinfunction "P$7_7") (pintype "bidirectional"))
      (node (ref "U$6") (pin "8") (pinfunction "P$8_8") (pintype "bidirectional"))
      (node (ref "U$6") (pin "9") (pinfunction "P$9_9") (pintype "bidirectional"))
      (node (ref "U$6") (pin "ANTENNA") (pinfunction "ANT_ANTENNA") (pintype "bidirectional"))
    )
    (net (code "49") (name "Net-(U$8-LX)") (class "Default")
      (node (ref "L4") (pin "1") (pinfunction "1_1") (pintype "bidirectional"))
      (node (ref "U$8") (pin "7") (pinfunction "LX_7") (pintype "bidirectional"))
    )
    (net (code "50") (name "unconnected-(GPS-GPIO1{slash}RXD1-Pad3)") (class "Default")
      (node (ref "GPS") (pin "3") (pinfunction "GPIO1/RXD1_3") (pintype "bidirectional"))
    )
    (net (code "51") (name "unconnected-(GPS-GPIO2{slash}TXD1-Pad8)") (class "Default")
      (node (ref "GPS") (pin "8") (pinfunction "GPIO2/TXD1_8") (pintype "bidirectional"))
    )
    (net (code "52") (name "unconnected-(GPS-GPIO3{slash}P1PPS1-Pad40)") (class "Default")
      (node (ref "GPS") (pin "40") (pinfunction "GPIO3/P1PPS1_40") (pintype "bidirectional"))
    )
    (net (code "53") (name "unconnected-(GPS-GPIO4{slash}SCL-Pad37)") (class "Default")
      (node (ref "GPS") (pin "37") (pinfunction "GPIO4/SCL_37") (pintype "bidirectional"))
    )
    (net (code "54") (name "unconnected-(GPS-GPIO5{slash}SDA-Pad14)") (class "Default")
      (node (ref "GPS") (pin "14") (pinfunction "GPIO5/SDA_14") (pintype "bidirectional"))
    )
    (net (code "55") (name "unconnected-(GPS-GPIO6{slash}M_CSN2-Pad13)") (class "Default")
      (node (ref "GPS") (pin "13") (pinfunction "GPIO6/M_CSN2_13") (pintype "bidirectional"))
    )
    (net (code "56") (name "unconnected-(GPS-GPIO7{slash}P1PPS2-Pad12)") (class "Default")
      (node (ref "GPS") (pin "12") (pinfunction "GPIO7/P1PPS2_12") (pintype "bidirectional"))
    )
    (net (code "57") (name "unconnected-(GPS-GPIO8-Pad51)") (class "Default")
      (node (ref "GPS") (pin "51") (pinfunction "GPIO8_51") (pintype "bidirectional"))
    )
    (net (code "58") (name "unconnected-(GPS-GPIO9-Pad47)") (class "Default")
      (node (ref "GPS") (pin "47") (pinfunction "GPIO9_47") (pintype "bidirectional"))
    )
    (net (code "59") (name "unconnected-(GPS-GPIO10-Pad59)") (class "Default")
      (node (ref "GPS") (pin "59") (pinfunction "GPIO10_59") (pintype "bidirectional"))
    )
    (net (code "60") (name "unconnected-(GPS-GPIO11-Pad63)") (class "Default")
      (node (ref "GPS") (pin "63") (pinfunction "GPIO11_63") (pintype "bidirectional"))
    )
    (net (code "61") (name "unconnected-(GPS-GPIO12-Pad55)") (class "Default")
      (node (ref "GPS") (pin "55") (pinfunction "GPIO12_55") (pintype "bidirectional"))
    )
    (net (code "62") (name "unconnected-(GPS-GPIO13-Pad50)") (class "Default")
      (node (ref "GPS") (pin "50") (pinfunction "GPIO13_50") (pintype "bidirectional"))
    )
    (net (code "63") (name "unconnected-(GPS-GPIO14-Pad45)") (class "Default")
      (node (ref "GPS") (pin "45") (pinfunction "GPIO14_45") (pintype "bidirectional"))
    )
    (net (code "64") (name "unconnected-(GPS-GPIO15-Pad53)") (class "Default")
      (node (ref "GPS") (pin "53") (pinfunction "GPIO15_53") (pintype "bidirectional"))
    )
    (net (code "65") (name "unconnected-(GPS-GPIO16-Pad48)") (class "Default")
      (node (ref "GPS") (pin "48") (pinfunction "GPIO16_48") (pintype "bidirectional"))
    )
    (net (code "66") (name "unconnected-(GPS-GPIO20-Pad54)") (class "Default")
      (node (ref "GPS") (pin "54") (pinfunction "GPIO20_54") (pintype "bidirectional"))
    )
    (net (code "67") (name "unconnected-(GPS-GPIO21-Pad57)") (class "Default")
      (node (ref "GPS") (pin "57") (pinfunction "GPIO21_57") (pintype "bidirectional"))
    )
    (net (code "68") (name "unconnected-(GPS-GPIO22-Pad46)") (class "Default")
      (node (ref "GPS") (pin "46") (pinfunction "GPIO22_46") (pintype "bidirectional"))
    )
    (net (code "69") (name "unconnected-(GPS-GPIO23{slash}M_CSN0-Pad16)") (class "Default")
      (node (ref "GPS") (pin "16") (pinfunction "GPIO23/M_CSN0_16") (pintype "bidirectional"))
    )
    (net (code "70") (name "unconnected-(GPS-GPIO24{slash}M_SCK-Pad5)") (class "Default")
      (node (ref "GPS") (pin "5") (pinfunction "GPIO24/M_SCK_5") (pintype "bidirectional"))
    )
    (net (code "71") (name "unconnected-(GPS-GPIO25{slash}M_MISO-Pad4)") (class "Default")
      (node (ref "GPS") (pin "4") (pinfunction "GPIO25/M_MISO_4") (pintype "bidirectional"))
    )
    (net (code "72") (name "unconnected-(GPS-GPIO26{slash}M_MOSI-Pad6)") (class "Default")
      (node (ref "GPS") (pin "6") (pinfunction "GPIO26/M_MOSI_6") (pintype "bidirectional"))
    )
    (net (code "73") (name "unconnected-(GPS-GPIO27-Pad52)") (class "Default")
      (node (ref "GPS") (pin "52") (pinfunction "GPIO27_52") (pintype "bidirectional"))
    )
    (net (code "74") (name "unconnected-(GPS-GPIO28{slash}MS_CSN-Pad43)") (class "Default")
      (node (ref "GPS") (pin "43") (pinfunction "GPIO28/MS_CSN_43") (pintype "bidirectional"))
    )
    (net (code "75") (name "unconnected-(GPS-GPIO29{slash}MS_SCK-Pad41)") (class "Default")
      (node (ref "GPS") (pin "41") (pinfunction "GPIO29/MS_SCK_41") (pintype "bidirectional"))
    )
    (net (code "76") (name "unconnected-(GPS-GPIO30{slash}MS_MOSI-Pad38)") (class "Default")
      (node (ref "GPS") (pin "38") (pinfunction "GPIO30/MS_MOSI_38") (pintype "bidirectional"))
    )
    (net (code "77") (name "unconnected-(GPS-GPIO31{slash}MS_MISO-Pad39)") (class "Default")
      (node (ref "GPS") (pin "39") (pinfunction "GPIO31/MS_MISO_39") (pintype "bidirectional"))
    )
    (net (code "78") (name "unconnected-(GPS-NC-Pad17)") (class "Default")
      (node (ref "GPS") (pin "17") (pinfunction "NC_17") (pintype "bidirectional"))
    )
    (net (code "79") (name "unconnected-(GPS-NC-Pad20)") (class "Default")
      (node (ref "GPS") (pin "20") (pinfunction "NC_20") (pintype "bidirectional"))
    )
    (net (code "80") (name "unconnected-(GPS-NC-Pad23)") (class "Default")
      (node (ref "GPS") (pin "23") (pinfunction "NC_23") (pintype "bidirectional"))
    )
    (net (code "81") (name "unconnected-(GPS-NC-Pad26)") (class "Default")
      (node (ref "GPS") (pin "26") (pinfunction "NC_26") (pintype "bidirectional"))
    )
    (net (code "82") (name "unconnected-(GPS-NC-Pad30)") (class "Default")
      (node (ref "GPS") (pin "30") (pinfunction "NC_30") (pintype "bidirectional"))
    )
    (net (code "83") (name "unconnected-(GPS-NC-Pad34)") (class "Default")
      (node (ref "GPS") (pin "34") (pinfunction "NC_34") (pintype "bidirectional"))
    )
    (net (code "84") (name "unconnected-(GPS-NC-Pad35)") (class "Default")
      (node (ref "GPS") (pin "35") (pinfunction "NC_35") (pintype "bidirectional"))
    )
    (net (code "85") (name "unconnected-(GPS-NC-Pad36)") (class "Default")
      (node (ref "GPS") (pin "36") (pinfunction "NC_36") (pintype "bidirectional"))
    )
    (net (code "86") (name "unconnected-(GPS-NC-Pad56)") (class "Default")
      (node (ref "GPS") (pin "56") (pinfunction "NC_56") (pintype "bidirectional"))
    )
    (net (code "87") (name "unconnected-(GPS-NC-Pad66)") (class "Default")
      (node (ref "GPS") (pin "66") (pinfunction "NC_66") (pintype "bidirectional"))
    )
    (net (code "88") (name "unconnected-(GPS-NC-Pad67)") (class "Default")
      (node (ref "GPS") (pin "67") (pinfunction "NC_67") (pintype "bidirectional"))
    )
    (net (code "89") (name "unconnected-(GPS-NC-Pad68)") (class "Default")
      (node (ref "GPS") (pin "68") (pinfunction "NC_68") (pintype "bidirectional"))
    )
    (net (code "90") (name "unconnected-(IMU-DEN_A{slash}G-Pad13)") (class "Default")
      (node (ref "IMU") (pin "13") (pinfunction "DEN_A/G_13") (pintype "bidirectional"))
    )
    (net (code "91") (name "unconnected-(IMU-INT_M-Pad10)") (class "Default")
      (node (ref "IMU") (pin "10") (pinfunction "INT_M_10") (pintype "bidirectional"))
    )
    (net (code "92") (name "unconnected-(MICROCONTROLLER-Pad14)") (class "Default")
      (node (ref "MICROCONTROLLER") (pin "14") (pinfunction "14_14") (pintype "bidirectional"))
    )
    (net (code "93") (name "unconnected-(MICROCONTROLLER-Pad15)") (class "Default")
      (node (ref "MICROCONTROLLER") (pin "15") (pinfunction "15_15") (pintype "bidirectional"))
    )
    (net (code "94") (name "unconnected-(MICROCONTROLLER-Pad16)") (class "Default")
      (node (ref "MICROCONTROLLER") (pin "16") (pinfunction "16_16") (pintype "bidirectional"))
    )
    (net (code "95") (name "unconnected-(MICROCONTROLLER-Pad17)") (class "Default")
      (node (ref "MICROCONTROLLER") (pin "17") (pinfunction "17_17") (pintype "bidirectional"))
    )
    (net (code "96") (name "unconnected-(MICROCONTROLLER-Pad21)") (class "Default")
      (node (ref "MICROCONTROLLER") (pin "21") (pinfunction "21_21") (pintype "bidirectional"))
    )
    (net (code "97") (name "unconnected-(MICROCONTROLLER-Pad29)") (class "Default")
      (node (ref "MICROCONTROLLER") (pin "29") (pinfunction "29_29") (pintype "bidirectional"))
    )
    (net (code "98") (name "unconnected-(MICROCONTROLLER-Pad30)") (class "Default")
      (node (ref "MICROCONTROLLER") (pin "30") (pinfunction "30_30") (pintype "bidirectional"))
    )
    (net (code "99") (name "unconnected-(MICROCONTROLLER-Pad31)") (class "Default")
      (node (ref "MICROCONTROLLER") (pin "31") (pinfunction "31_31") (pintype "bidirectional"))
    )
    (net (code "100") (name "unconnected-(MICROCONTROLLER-Pad38)") (class "Default")
      (node (ref "MICROCONTROLLER") (pin "38") (pinfunction "38_38") (pintype "bidirectional"))
    )
    (net (code "101") (name "unconnected-(MICROCONTROLLER-Pad39)") (class "Default")
      (node (ref "MICROCONTROLLER") (pin "39") (pinfunction "39_39") (pintype "input"))
    )
    (net (code "102") (name "unconnected-(MICROCONTROLLER-Pad42)") (class "Default")
      (node (ref "MICROCONTROLLER") (pin "42") (pinfunction "42_42") (pintype "bidirectional"))
    )
    (net (code "103") (name "unconnected-(MICROCONTROLLER-Pad43)") (class "Default")
      (node (ref "MICROCONTROLLER") (pin "43") (pinfunction "43_43") (pintype "bidirectional"))
    )
    (net (code "104") (name "unconnected-(U$5-PadNC)") (class "Default")
      (node (ref "U$5") (pin "NC") (pinfunction "NC_NC") (pintype "bidirectional"))
    )
    (net (code "105") (name "unconnected-(U$8-LBI-Pad2)") (class "Default")
      (node (ref "U$8") (pin "2") (pinfunction "LBI_2") (pintype "bidirectional"))
    )
    (net (code "106") (name "unconnected-(U$8-LBO-Pad3)") (class "Default")
      (node (ref "U$8") (pin "3") (pinfunction "LBO_3") (pintype "bidirectional"))
    )
    (net (code "107") (name "unconnected-(U$8-REF-Pad4)") (class "Default")
      (node (ref "U$8") (pin "4") (pinfunction "REF_4") (pintype "bidirectional"))
    )
  )
)
